# usb.net
KiCad netlist of a schematic drawn in EAGLE
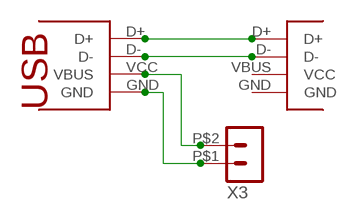
[diagram p0: schematic, sheet 1]

(export (version "E")
  (design (tool "Eeschema 10.0.6"))
  (components
    (comp (ref "U$1")
      (value "USB-A_FEM")
      (footprint "eagle-import:USB-A-S")
      (libsource (lib "eagle-import") (part "USB-A_FEM"))
    )
    (comp (ref "U$2")
      (value "USB-A-PLUG")
      (footprint "eagle-import:USB-A-H")
      (libsource (lib "eagle-import") (part "USB-A-PLUG"))
    )
    (comp (ref "X3")
      (value "HEADER_POS2_43045-0206")
      (footprint "eagle-import:43045-0206")
      (libsource (lib "eagle-import") (part "HEADER_POS2_?43045-0206"))
    )
  )
  (nets
    (net (code "1") (name "Net-(U$1-PadD+)") (class "Default")
      (node (ref "U$1") (pin "D+") (pinfunction "D+_D+") (pintype "bidirectional"))
      (node (ref "U$2") (pin "D+") (pinfunction "D+_D+") (pintype "bidirectional"))
    )
    (net (code "2") (name "Net-(U$1-PadD-)") (class "Default")
      (node (ref "U$1") (pin "D-") (pinfunction "D-_D-") (pintype "bidirectional"))
      (node (ref "U$2") (pin "D-") (pinfunction "D-_D-") (pintype "bidirectional"))
    )
    (net (code "3") (name "Net-(U$1-VBUS)") (class "Default")
      (node (ref "U$1") (pin "VCC") (pinfunction "VBUS_VCC") (pintype "bidirectional"))
      (node (ref "X3") (pin "P$2") (pinfunction "2_P$2") (pintype "passive"))
    )
    (net (code "4") (name "Net-(X3-1)") (class "Default")
      (node (ref "U$1") (pin "GND") (pinfunction "GND_GND") (pintype "bidirectional"))
      (node (ref "X3") (pin "P$1") (pinfunction "1_P$1") (pintype "passive"))
    )
    (net (code "5") (name "unconnected-(U$2-PadGND)") (class "Default")
      (node (ref "U$2") (pin "GND") (pinfunction "GND_GND") (pintype "bidirectional"))
    )
    (net (code "6") (name "unconnected-(U$2-VCC-PadVBUS)") (class "Default")
      (node (ref "U$2") (pin "VBUS") (pinfunction "VCC_VBUS") (pintype "bidirectional"))
    )
  )
)
